# Sheet4.net
KiCad netlist of a schematic drawn in Altium Designer
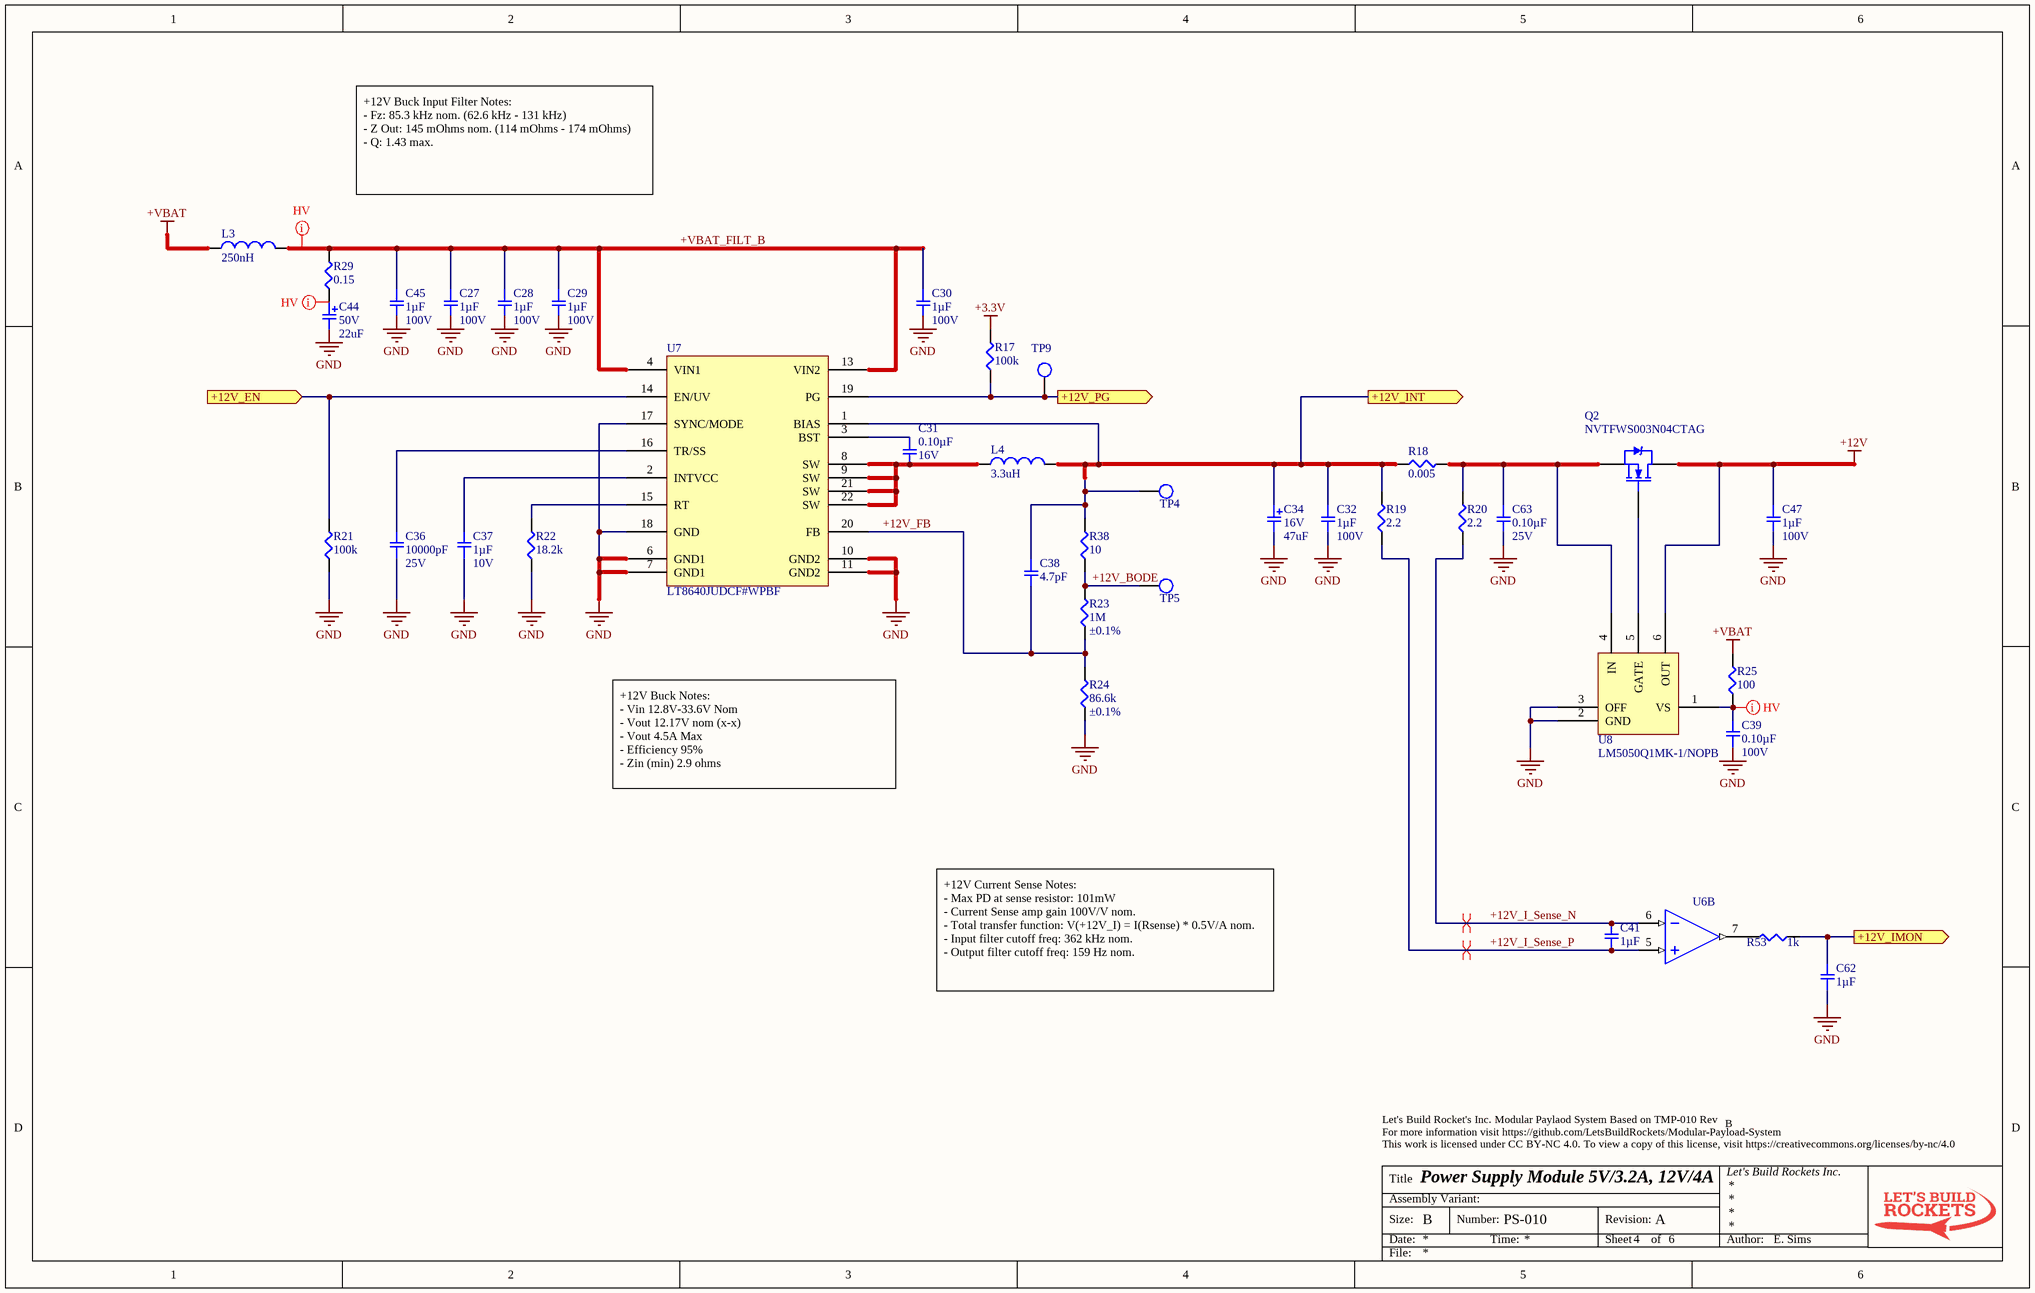
[diagram p0: Sheet4.SchDoc]

(export (version "E")
  (design (tool "Eeschema 10.0.6"))
  (components
    (comp (ref "C27")
      (value "1µF")
      (footprint "SMD-0805C")
      (description "CAP CER 1UF 100V X7S 0805")
      (fields
        (field (name "DIGI-KEY PART NUMBER") "490-10918-1-ND")
        (field (name "PART NUMBER") "GRJ21BC72A105KE11L")
        (field (name "VOLTAGE") "100V")
      )
      (libsource (lib "capacitor_murata_0805") (part "GRJ21BC72A105KE11L"))
    )
    (comp (ref "C28")
      (value "1µF")
      (footprint "SMD-0805C")
      (description "CAP CER 1UF 100V X7S 0805")
      (fields
        (field (name "DIGI-KEY PART NUMBER") "490-10918-1-ND")
        (field (name "PART NUMBER") "GRJ21BC72A105KE11L")
        (field (name "VOLTAGE") "100V")
      )
      (libsource (lib "capacitor_murata_0805") (part "GRJ21BC72A105KE11L"))
    )
    (comp (ref "C29")
      (value "1µF")
      (footprint "SMD-0805C")
      (description "CAP CER 1UF 100V X7S 0805")
      (fields
        (field (name "DIGI-KEY PART NUMBER") "490-10918-1-ND")
        (field (name "PART NUMBER") "GRJ21BC72A105KE11L")
        (field (name "VOLTAGE") "100V")
      )
      (libsource (lib "capacitor_murata_0805") (part "GRJ21BC72A105KE11L"))
    )
    (comp (ref "C30")
      (value "1µF")
      (footprint "SMD-0805C")
      (description "CAP CER 1UF 100V X7S 0805")
      (fields
        (field (name "DIGI-KEY PART NUMBER") "490-10918-1-ND")
        (field (name "PART NUMBER") "GRJ21BC72A105KE11L")
        (field (name "VOLTAGE") "100V")
      )
      (libsource (lib "capacitor_murata_0805") (part "GRJ21BC72A105KE11L"))
    )
    (comp (ref "C31")
      (value "0.10µF")
      (footprint "SMD-0402C")
      (description "CAP CER 0.1UF 16V X7R 0402")
      (fields
        (field (name "DIGI-KEY PART NUMBER") "490-4759-1-ND")
        (field (name "PART NUMBER") "GCM155R71C104KA55D")
        (field (name "VOLTAGE") "16V")
      )
      (libsource (lib "capacitor_murata_0402") (part "GCM155R71C104KA55D"))
    )
    (comp (ref "C32")
      (value "1µF")
      (footprint "SMD-0805C")
      (description "CAP CER 1UF 100V X7S 0805")
      (fields
        (field (name "DIGI-KEY PART NUMBER") "490-10918-1-ND")
        (field (name "PART NUMBER") "GRJ21BC72A105KE11L")
        (field (name "VOLTAGE") "100V")
      )
      (libsource (lib "capacitor_murata_0805") (part "GRJ21BC72A105KE11L"))
    )
    (comp (ref "C34")
      (value "47uF")
      (footprint "KEMET W - CAPMP7343X15N")
      (fields (field (name "VOLTAGE") "16V") (field (name "Comment") "T521W476M016ATE045"))
      (libsource (lib "KEMET") (part "T521W476M016ATE045"))
    )
    (comp (ref "C36")
      (value "10000pF")
      (footprint "SMD-0402C")
      (description "CAP CER 10000PF 25V X7R 0402")
      (fields
        (field (name "DIGI-KEY PART NUMBER") "490-6043-1-ND")
        (field (name "PART NUMBER") "GCM155R71E103KA37D")
        (field (name "VOLTAGE") "25V")
      )
      (libsource (lib "capacitor_murata_0402") (part "GCM155R71E103KA37D"))
    )
    (comp (ref "C37")
      (value "1µF")
      (footprint "SMD-0402C")
      (description "CAP CER 1UF 10V X7S 0402")
      (fields
        (field (name "DIGI-KEY PART NUMBER") "490-13409-1-ND")
        (field (name "PART NUMBER") "GCM155C71A105KE38D")
        (field (name "VOLTAGE") "10V")
      )
      (libsource (lib "capacitor_murata_0402") (part "GCM155C71A105KE38D"))
    )
    (comp (ref "C38")
      (value "4.7pF")
      (footprint "SMD-0402C")
      (description "CAP CER 4.7PF 50V NP0 0402")
      (fields
        (field (name "DIGI-KEY PART NUMBER") "490-12652-1-ND")
        (field (name "PART NUMBER") "GCM1555C1H4R7CA16D")
      )
      (libsource (lib "capacitor_murata_0402") (part "GCM1555C1H4R7CA16D"))
    )
    (comp (ref "C39")
      (value "0.10µF")
      (footprint "SMD-0603C")
      (description "CAP CER 0.1UF 100V X7R 0603")
      (fields
        (field (name "DIGI-KEY PART NUMBER") "490-3285-1-ND")
        (field (name "PART NUMBER") "GRM188R72A104KA35D")
        (field (name "VOLTAGE") "100V")
      )
      (libsource (lib "capacitor_murata_0603") (part "GRM188R72A104KA35D"))
    )
    (comp (ref "C41")
      (value "1µF")
      (footprint "SMD-0402C")
      (description "CAP CER 1UF 10V X7S 0402")
      (fields
        (field (name "DIGI-KEY PART NUMBER") "490-13409-1-ND")
        (field (name "PART NUMBER") "GCM155C71A105KE38D")
      )
      (libsource (lib "capacitor_murata_0402") (part "GCM155C71A105KE38D"))
    )
    (comp (ref "C44")
      (value "22uF")
      (footprint "KEMET D - CAPMP7343X31N")
      (fields (field (name "VOLTAGE") "50V") (field (name "Comment") "T521D226M050ATE090"))
      (libsource (lib "KEMET") (part "T521D226M050ATE090"))
    )
    (comp (ref "C45")
      (value "1µF")
      (footprint "SMD-0805C")
      (description "CAP CER 1UF 100V X7S 0805")
      (fields
        (field (name "DIGI-KEY PART NUMBER") "490-10918-1-ND")
        (field (name "PART NUMBER") "GRJ21BC72A105KE11L")
        (field (name "VOLTAGE") "100V")
      )
      (libsource (lib "capacitor_murata_0805") (part "GRJ21BC72A105KE11L"))
    )
    (comp (ref "C47")
      (value "1µF")
      (footprint "SMD-0805C")
      (description "CAP CER 1UF 100V X7S 0805")
      (fields
        (field (name "DIGI-KEY PART NUMBER") "490-10918-1-ND")
        (field (name "PART NUMBER") "GRJ21BC72A105KE11L")
        (field (name "VOLTAGE") "100V")
      )
      (libsource (lib "capacitor_murata_0805") (part "GRJ21BC72A105KE11L"))
    )
    (comp (ref "C62")
      (value "1µF")
      (footprint "SMD-0402C")
      (description "CAP CER 1UF 10V X7S 0402")
      (fields
        (field (name "DIGI-KEY PART NUMBER") "490-13409-1-ND")
        (field (name "PART NUMBER") "GCM155C71A105KE38D")
      )
      (libsource (lib "capacitor_murata_0402") (part "GCM155C71A105KE38D"))
    )
    (comp (ref "C63")
      (value "0.10µF")
      (footprint "SMD-0603C")
      (description "CAP CER 0.1UF 25V X7R 0603")
      (fields
        (field (name "DIGI-KEY PART NUMBER") "490-6051-1-ND")
        (field (name "PART NUMBER") "GCM188R71E104KA57D")
        (field (name "VOLTAGE") "25V")
      )
      (libsource (lib "capacitor_murata_0603") (part "GCM188R71E104KA57D"))
    )
    (comp (ref "L3")
      (value "250nH")
      (footprint "INDM4040X21N (XGL4020)")
      (fields (field (name "Comment") "XGL4020-251ME"))
      (libsource (lib "ModularPayload") (part "XGL4020-251ME"))
    )
    (comp (ref "L4")
      (value "3.3uH")
      (footprint "INDM7050X50N (Wurth)")
      (fields (field (name "TOLERANCE") "20%") (field (name "Comment") "744314330"))
      (libsource (lib "ModularPayload") (part "744314330"))
    )
    (comp (ref "Q2")
      (value "NVTFWS003N04CTAG")
      (footprint "DFN065P305X80-8N")
      (libsource (lib "ModularPayload") (part "NVTFWS003N04CTAG"))
    )
    (comp (ref "R17")
      (value "100k")
      (footprint "SMD-0402-RES")
      (description "RES SMD 100K OHM 5% 1/10W 0402")
      (fields (field (name "PART NUMBER") "ERJ-2GEJ104X") (field (name "DIGI-KEY PART NUMBER") "P100KJCT-ND"))
      (libsource (lib "Panasonic_ERJ_0402") (part "ERJ-2GEJ104X"))
    )
    (comp (ref "R18")
      (value "0.005")
      (footprint "SMD-0603-RES")
      (description "RES SMD 0.005 OHM 1% 1/4W 0603")
      (fields
        (field (name "PART NUMBER") "ERJ-3LWFR005V")
        (field (name "DIGI-KEY PART NUMBER") "P19182CT-ND")
      )
      (libsource (lib "Panasonic_ERJ_0603") (part "ERJ-3LWFR005V"))
    )
    (comp (ref "R19")
      (value "2.2")
      (footprint "SMD-0603-RES")
      (description "RES SMD 2.2 OHM 1% 1/10W 0603")
      (fields (field (name "PART NUMBER") "ERJ-3RQF2R2V") (field (name "DIGI-KEY PART NUMBER") "P2.2AJCT-ND"))
      (libsource (lib "Panasonic_ERJ_0603") (part "ERJ-3RQF2R2V"))
    )
    (comp (ref "R20")
      (value "2.2")
      (footprint "SMD-0603-RES")
      (description "RES SMD 2.2 OHM 1% 1/10W 0603")
      (fields (field (name "PART NUMBER") "ERJ-3RQF2R2V") (field (name "DIGI-KEY PART NUMBER") "P2.2AJCT-ND"))
      (libsource (lib "Panasonic_ERJ_0603") (part "ERJ-3RQF2R2V"))
    )
    (comp (ref "R21")
      (value "100k")
      (footprint "SMD-0402-RES")
      (description "RES SMD 100K OHM 5% 1/10W 0402")
      (fields (field (name "PART NUMBER") "ERJ-2GEJ104X") (field (name "DIGI-KEY PART NUMBER") "P100KJCT-ND"))
      (libsource (lib "Panasonic_ERJ_0402") (part "ERJ-2GEJ104X"))
    )
    (comp (ref "R22")
      (value "18.2k")
      (footprint "SMD-0402-RES")
      (description "RES SMD 18.2K OHM 1% 1/10W 0402")
      (fields
        (field (name "PART NUMBER") "ERJ-2RKF1822X")
        (field (name "DIGI-KEY PART NUMBER") "P18.2KLCT-ND")
      )
      (libsource (lib "Panasonic_ERJ_0402") (part "ERJ-2RKF1822X"))
    )
    (comp (ref "R23")
      (value "1M")
      (footprint "SMD-0805-RES")
      (description "RES SMD 1M OHM 0.1% 1/4W 0805")
      (fields
        (field (name "PART NUMBER") "ERJ-PB6B1004V")
        (field (name "DIGI-KEY PART NUMBER") "P20936CT-ND")
        (field (name "TOLERANCE") "±0.1%")
      )
      (libsource (lib "Panasonic_ERJ_0805") (part "ERJ-PB6B1004V"))
    )
    (comp (ref "R24")
      (value "86.6k")
      (footprint "SMD-0805-RES")
      (description "RES SMD 86.6K OHM 0.1% 1/4W 0805")
      (fields
        (field (name "PART NUMBER") "ERJ-PB6B8662V")
        (field (name "DIGI-KEY PART NUMBER") "P20815CT-ND")
        (field (name "TOLERANCE") "±0.1%")
      )
      (libsource (lib "Panasonic_ERJ_0805") (part "ERJ-PB6B8662V"))
    )
    (comp (ref "R25")
      (value "100")
      (footprint "SMD-0402-RES")
      (description "RES SMD 100 OHM 5% 1/10W 0402")
      (fields (field (name "PART NUMBER") "ERJ-2GEJ101X") (field (name "DIGI-KEY PART NUMBER") "P100JCT-ND"))
      (libsource (lib "Panasonic_ERJ_0402") (part "ERJ-2GEJ101X"))
    )
    (comp (ref "R29")
      (value "0.15")
      (footprint "SMD-0603-RES")
      (description "RES SMD 0.15 OHM 5% 1/4W 0603")
      (fields (field (name "PART NUMBER") "ERJ-3BSJR15V") (field (name "DIGI-KEY PART NUMBER") "P17248CT-ND"))
      (libsource (lib "Panasonic_ERJ_0603") (part "ERJ-3BSJR15V"))
    )
    (comp (ref "R38")
      (value "10")
      (footprint "SMD-0402-RES")
      (description "RES SMD 10 OHM 5% 1/10W 0402")
      (fields (field (name "PART NUMBER") "ERJ-2GEJ100X") (field (name "DIGI-KEY PART NUMBER") "P10JCT-ND"))
      (libsource (lib "Panasonic_ERJ_0402") (part "ERJ-2GEJ100X"))
    )
    (comp (ref "R53")
      (value "1k")
      (footprint "SMD-0402-RES")
      (description "RES SMD 1K OHM 5% 1/10W 0402")
      (fields (field (name "PART NUMBER") "ERJ-2GEJ102X") (field (name "DIGI-KEY PART NUMBER") "P1.0KJCT-ND"))
      (libsource (lib "Panasonic_ERJ_0402") (part "ERJ-2GEJ102X"))
    )
    (comp (ref "TP4") (value "TP") (footprint "TP_SMD_40") (libsource (lib "TP") (part "TP")))
    (comp (ref "TP5") (value "TP") (footprint "TP_SMD_40") (libsource (lib "TP") (part "TP")))
    (comp (ref "TP9") (value "TP") (footprint "TP_SMD_40") (libsource (lib "TP") (part "TP")))
    (comp (ref "U6")
      (value "INA2180A3IDGKT")
      (footprint "TSOP65P490X110-8N")
      (libsource (lib "ModularPayload") (part "INA2180A3IDGKT"))
    )
    (comp (ref "U7")
      (value "LT8640JUDCF#WPBF")
      (footprint "QFN50P300X400X80_HS-21N (LT8640)")
      (libsource (lib "ModularPayload") (part "LT8640JUDCF#WPBF"))
    )
    (comp (ref "U8")
      (value "LM5050Q1MK-1/NOPB")
      (footprint "SOT95P280X110-6N")
      (libsource (lib "ModularPayload") (part "LM5050Q1MK-1/NOPB"))
    )
  )
  (nets
    (net (code "1") (name "+3.3V") (class "Default")
      (node (ref "R17") (pin "2") (pinfunction "2_2") (pintype "passive"))
    )
    (net (code "2") (name "+12V") (class "Default")
      (node (ref "C47") (pin "1") (pinfunction "1_1") (pintype "passive"))
      (node (ref "Q2") (pin "D") (pinfunction "D_D") (pintype "passive"))
      (node (ref "U8") (pin "6") (pinfunction "OUT_6") (pintype "passive"))
    )
    (net (code "3") (name "+VBAT") (class "Default")
      (node (ref "L3") (pin "1") (pinfunction "1_1") (pintype "passive"))
      (node (ref "R25") (pin "2") (pinfunction "2_2") (pintype "passive"))
    )
    (net (code "4") (name "/+12V_BODE") (class "Default")
      (node (ref "R23") (pin "2") (pinfunction "2_2") (pintype "passive"))
      (node (ref "R38") (pin "1") (pinfunction "1_1") (pintype "passive"))
      (node (ref "TP5") (pin "1") (pintype "passive"))
    )
    (net (code "5") (name "/+12V_EN") (class "Default")
      (node (ref "R21") (pin "2") (pinfunction "2_2") (pintype "passive"))
      (node (ref "U7") (pin "14") (pinfunction "EN/UV_14") (pintype "passive"))
    )
    (net (code "6") (name "/+12V_FB") (class "Default")
      (node (ref "C38") (pin "2") (pinfunction "2_2") (pintype "passive"))
      (node (ref "R23") (pin "1") (pinfunction "1_1") (pintype "passive"))
      (node (ref "R24") (pin "2") (pinfunction "2_2") (pintype "passive"))
      (node (ref "U7") (pin "20") (pinfunction "FB_20") (pintype "passive"))
    )
    (net (code "7") (name "/+12V_IMON") (class "Default")
      (node (ref "C62") (pin "2") (pinfunction "2_2") (pintype "passive"))
      (node (ref "R53") (pin "1") (pinfunction "1_1") (pintype "passive"))
    )
    (net (code "8") (name "/+12V_INT") (class "Default")
      (node (ref "C32") (pin "1") (pinfunction "1_1") (pintype "passive"))
      (node (ref "C34") (pin "1") (pinfunction "1_1") (pintype "passive"))
      (node (ref "C38") (pin "1") (pinfunction "1_1") (pintype "passive"))
      (node (ref "L4") (pin "2") (pinfunction "2_2") (pintype "passive"))
      (node (ref "R18") (pin "1") (pinfunction "1_1") (pintype "passive"))
      (node (ref "R19") (pin "2") (pinfunction "2_2") (pintype "passive"))
      (node (ref "R38") (pin "2") (pinfunction "2_2") (pintype "passive"))
      (node (ref "TP4") (pin "1") (pintype "passive"))
      (node (ref "U7") (pin "1") (pinfunction "BIAS_1") (pintype "passive"))
    )
    (net (code "9") (name "/+12V_I_Sense_N") (class "Default")
      (node (ref "C41") (pin "2") (pinfunction "2_2") (pintype "passive"))
      (node (ref "R20") (pin "1") (pinfunction "1_1") (pintype "passive"))
      (node (ref "U6") (pin "6") (pinfunction "IN-2_6") (pintype "input"))
    )
    (net (code "10") (name "/+12V_I_Sense_P") (class "Default")
      (node (ref "C41") (pin "1") (pinfunction "1_1") (pintype "passive"))
      (node (ref "R19") (pin "1") (pinfunction "1_1") (pintype "passive"))
      (node (ref "U6") (pin "5") (pinfunction "IN+2_5") (pintype "input"))
    )
    (net (code "11") (name "/+12V_PG") (class "Default")
      (node (ref "R17") (pin "1") (pinfunction "1_1") (pintype "passive"))
      (node (ref "TP9") (pin "1") (pintype "passive"))
      (node (ref "U7") (pin "19") (pinfunction "PG_19") (pintype "passive"))
    )
    (net (code "12") (name "/+VBAT_FILT_B") (class "Default")
      (node (ref "C27") (pin "1") (pinfunction "1_1") (pintype "passive"))
      (node (ref "C28") (pin "1") (pinfunction "1_1") (pintype "passive"))
      (node (ref "C29") (pin "1") (pinfunction "1_1") (pintype "passive"))
      (node (ref "C30") (pin "1") (pinfunction "1_1") (pintype "passive"))
      (node (ref "C45") (pin "1") (pinfunction "1_1") (pintype "passive"))
      (node (ref "L3") (pin "2") (pinfunction "2_2") (pintype "passive"))
      (node (ref "R29") (pin "2") (pinfunction "2_2") (pintype "passive"))
      (node (ref "U7") (pin "13") (pinfunction "VIN2_13") (pintype "passive"))
      (node (ref "U7") (pin "4") (pinfunction "VIN1_4") (pintype "passive"))
    )
    (net (code "13") (name "GND") (class "Default")
      (node (ref "C27") (pin "2") (pinfunction "2_2") (pintype "passive"))
      (node (ref "C28") (pin "2") (pinfunction "2_2") (pintype "passive"))
      (node (ref "C29") (pin "2") (pinfunction "2_2") (pintype "passive"))
      (node (ref "C30") (pin "2") (pinfunction "2_2") (pintype "passive"))
      (node (ref "C32") (pin "2") (pinfunction "2_2") (pintype "passive"))
      (node (ref "C34") (pin "2") (pinfunction "2_2") (pintype "passive"))
      (node (ref "C36") (pin "1") (pinfunction "1_1") (pintype "passive"))
      (node (ref "C37") (pin "1") (pinfunction "1_1") (pintype "passive"))
      (node (ref "C39") (pin "1") (pinfunction "1_1") (pintype "passive"))
      (node (ref "C44") (pin "2") (pinfunction "2_2") (pintype "passive"))
      (node (ref "C45") (pin "2") (pinfunction "2_2") (pintype "passive"))
      (node (ref "C47") (pin "2") (pinfunction "2_2") (pintype "passive"))
      (node (ref "C62") (pin "1") (pinfunction "1_1") (pintype "passive"))
      (node (ref "C63") (pin "2") (pinfunction "2_2") (pintype "passive"))
      (node (ref "R21") (pin "1") (pinfunction "1_1") (pintype "passive"))
      (node (ref "R22") (pin "1") (pinfunction "1_1") (pintype "passive"))
      (node (ref "R24") (pin "1") (pinfunction "1_1") (pintype "passive"))
      (node (ref "U7") (pin "10") (pinfunction "GND2_10") (pintype "passive"))
      (node (ref "U7") (pin "11") (pinfunction "GND2_11") (pintype "passive"))
      (node (ref "U7") (pin "17") (pinfunction "SYNC/MODE_17") (pintype "passive"))
      (node (ref "U7") (pin "18") (pinfunction "GND_18") (pintype "passive"))
      (node (ref "U7") (pin "6") (pinfunction "GND1_6") (pintype "passive"))
      (node (ref "U7") (pin "7") (pinfunction "GND1_7") (pintype "passive"))
      (node (ref "U8") (pin "2") (pinfunction "GND_2") (pintype "passive"))
      (node (ref "U8") (pin "3") (pinfunction "OFF_3") (pintype "passive"))
    )
    (net (code "14") (name "Net-(C31-Pad2)") (class "Default")
      (node (ref "C31") (pin "2") (pinfunction "2_2") (pintype "passive"))
      (node (ref "L4") (pin "1") (pinfunction "1_1") (pintype "passive"))
      (node (ref "U7") (pin "21") (pinfunction "SW_21") (pintype "passive"))
      (node (ref "U7") (pin "22") (pinfunction "SW_22") (pintype "passive"))
      (node (ref "U7") (pin "8") (pinfunction "SW_8") (pintype "passive"))
      (node (ref "U7") (pin "9") (pinfunction "SW_9") (pintype "passive"))
    )
    (net (code "15") (name "Net-(C44-Pad1)") (class "Default")
      (node (ref "C44") (pin "1") (pinfunction "1_1") (pintype "passive"))
      (node (ref "R29") (pin "1") (pinfunction "1_1") (pintype "passive"))
    )
    (net (code "16") (name "Net-(U6B-OUT2)") (class "Default")
      (node (ref "R53") (pin "2") (pinfunction "2_2") (pintype "passive"))
      (node (ref "U6") (pin "7") (pinfunction "OUT2_7") (pintype "output"))
    )
    (net (code "17") (name "Net-(U7-BST)") (class "Default")
      (node (ref "C31") (pin "1") (pinfunction "1_1") (pintype "passive"))
      (node (ref "U7") (pin "3") (pinfunction "BST_3") (pintype "passive"))
    )
    (net (code "18") (name "Net-(U7-INTVCC)") (class "Default")
      (node (ref "C37") (pin "2") (pinfunction "2_2") (pintype "passive"))
      (node (ref "U7") (pin "2") (pinfunction "INTVCC_2") (pintype "passive"))
    )
    (net (code "19") (name "Net-(U7-RT)") (class "Default")
      (node (ref "R22") (pin "2") (pinfunction "2_2") (pintype "passive"))
      (node (ref "U7") (pin "15") (pinfunction "RT_15") (pintype "passive"))
    )
    (net (code "20") (name "Net-(U7-TR{slash}SS)") (class "Default")
      (node (ref "C36") (pin "2") (pinfunction "2_2") (pintype "passive"))
      (node (ref "U7") (pin "16") (pinfunction "TR/SS_16") (pintype "passive"))
    )
    (net (code "21") (name "Net-(U8-GATE)") (class "Default")
      (node (ref "Q2") (pin "G") (pinfunction "G_G") (pintype "passive"))
      (node (ref "U8") (pin "5") (pinfunction "GATE_5") (pintype "passive"))
    )
    (net (code "22") (name "Net-(U8-IN)") (class "Default")
      (node (ref "C63") (pin "1") (pinfunction "1_1") (pintype "passive"))
      (node (ref "Q2") (pin "S") (pinfunction "S_S") (pintype "passive"))
      (node (ref "R18") (pin "2") (pinfunction "2_2") (pintype "passive"))
      (node (ref "R20") (pin "2") (pinfunction "2_2") (pintype "passive"))
      (node (ref "U8") (pin "4") (pinfunction "IN_4") (pintype "passive"))
    )
    (net (code "23") (name "Net-(U8-VS)") (class "Default")
      (node (ref "C39") (pin "2") (pinfunction "2_2") (pintype "passive"))
      (node (ref "R25") (pin "1") (pinfunction "1_1") (pintype "passive"))
      (node (ref "U8") (pin "1") (pinfunction "VS_1") (pintype "passive"))
    )
  )
)
